# LCD_Controler_SCH.net
KiCad netlist of a schematic drawn in Altium Designer
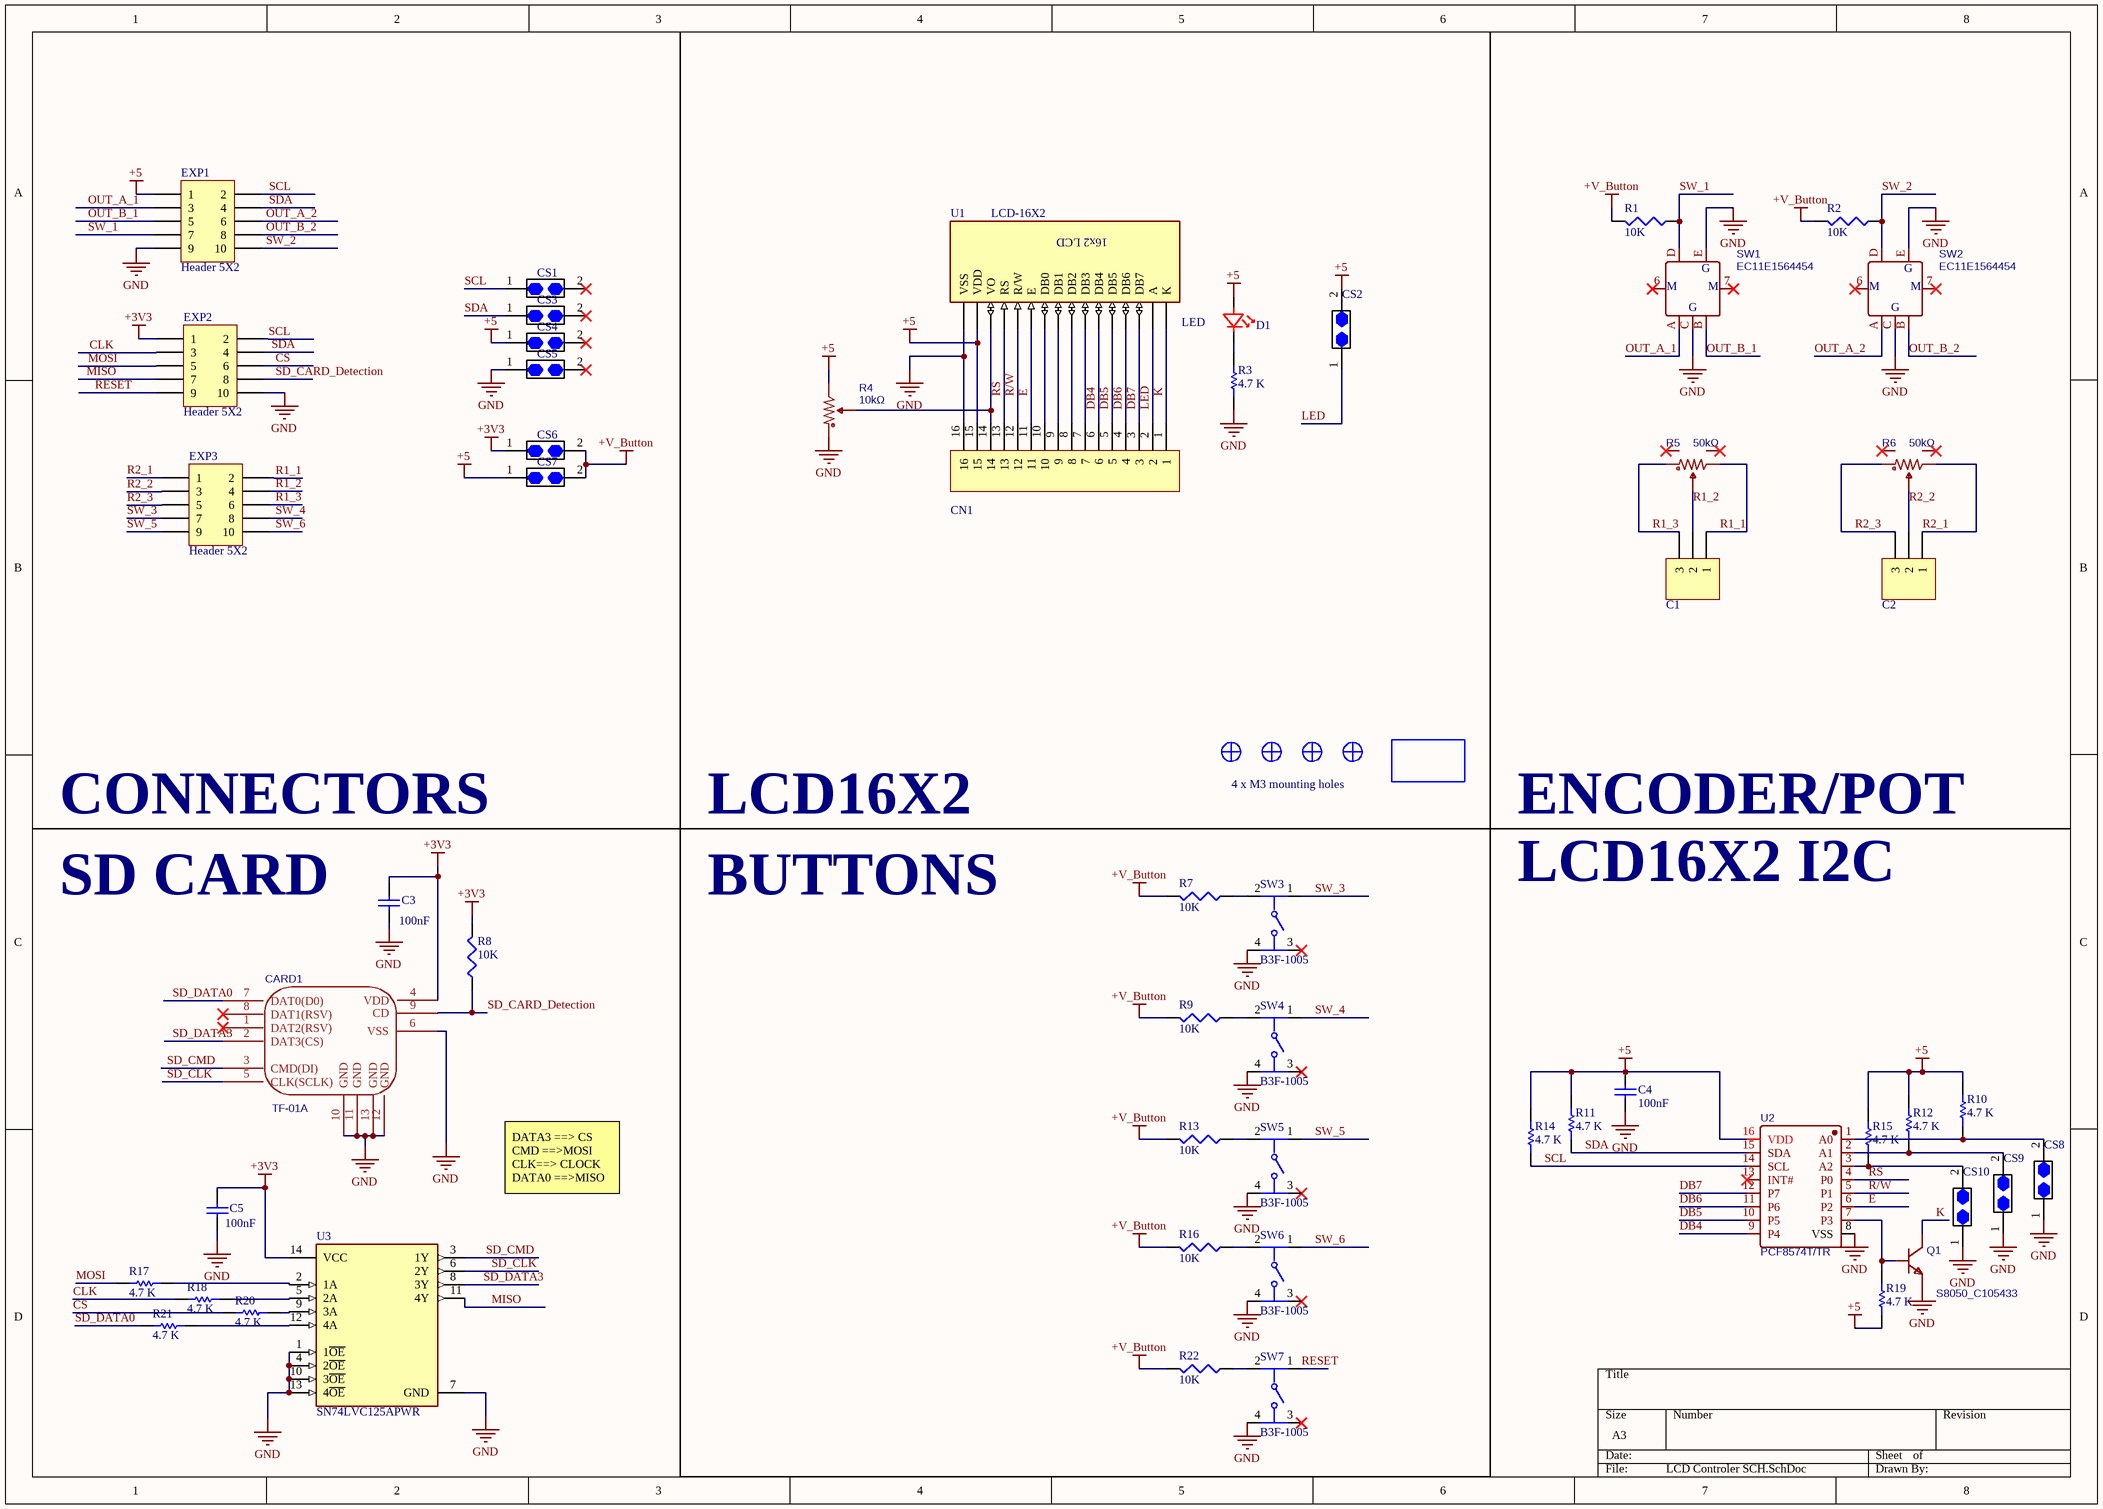
[diagram p0: LCD Controler SCH.SchDoc]

(export (version "E")
  (design (tool "Eeschema 10.0.6"))
  (components
    (comp (ref "C1")
      (value "Header 3")
      (footprint "HDR1X3-HEADER")
      (description "Header, 3-Pin")
      (fields (field (name "PUBLISHER") "Altium Limited"))
      (libsource (lib "Mylib") (part "Header 3"))
    )
    (comp (ref "C2")
      (value "Header 3")
      (footprint "HDR1X3-HEADER")
      (description "Header, 3-Pin")
      (fields (field (name "PUBLISHER") "Altium Limited"))
      (libsource (lib "Mylib") (part "Header 3"))
    )
    (comp (ref "C3")
      (value "100nF")
      (footprint "Cap 1608-0603")
      (description "CAP CER 0.1UF 50V X7R 0603/0805")
      (fields (field (name "MFR") "TORCH") (field (name "LCSC PART NUMBER") "C138340"))
      (libsource (lib "RUMBA_v2") (part "CapC-0603-100nF"))
    )
    (comp (ref "C4")
      (value "100nF")
      (footprint "Cap 1608-0603")
      (description "CAP CER 0.1UF 50V X7R 0603/0805")
      (fields (field (name "MFR") "TORCH") (field (name "LCSC PART NUMBER") "C138340"))
      (libsource (lib "RUMBA_v2") (part "CapC-0603-100nF"))
    )
    (comp (ref "C5")
      (value "100nF")
      (footprint "Cap 1608-0603")
      (description "CAP CER 0.1UF 50V X7R 0603/0805")
      (fields (field (name "MFR") "TORCH") (field (name "LCSC PART NUMBER") "C138340"))
      (libsource (lib "RUMBA_v2") (part "CapC-0603-100nF"))
    )
    (comp (ref "CARD1")
      (value "TF-01A")
      (footprint "TF-SMD_TF-01A2")
      (description "LCSC Part # C91145\r\nManufacturer Korean Hroparts Elec")
      (fields (field (name "BOM_SUPPLIER PART") "C91145"))
      (libsource (lib "Rumba_plus_esp") (part "TF-01A"))
    )
    (comp (ref "CN1")
      (value "Header 16")
      (footprint "HDR1X16-HEADER")
      (description "male")
      (fields (field (name "PUBLISHER") "Altium Limited"))
      (libsource (lib "Mylib") (part "Header 16x1"))
    )
    (comp (ref "CS1") (value "CHEVRON") (footprint "CHEV") (libsource (lib "Mylib") (part "CHEVRON")))
    (comp (ref "CS2") (value "CHEVRON") (footprint "CHEV") (libsource (lib "Mylib") (part "CHEVRON")))
    (comp (ref "CS3") (value "CHEVRON") (footprint "CHEV") (libsource (lib "Mylib") (part "CHEVRON")))
    (comp (ref "CS4") (value "CHEVRON") (footprint "CHEV") (libsource (lib "Mylib") (part "CHEVRON")))
    (comp (ref "CS5") (value "CHEVRON") (footprint "CHEV") (libsource (lib "Mylib") (part "CHEVRON")))
    (comp (ref "CS6") (value "CHEVRON") (footprint "CHEV") (libsource (lib "Mylib") (part "CHEVRON")))
    (comp (ref "CS7") (value "CHEVRON") (footprint "CHEV") (libsource (lib "Mylib") (part "CHEVRON")))
    (comp (ref "CS8") (value "CHEVRON") (footprint "CHEV") (libsource (lib "Mylib") (part "CHEVRON")))
    (comp (ref "CS9") (value "CHEVRON") (footprint "CHEV") (libsource (lib "Mylib") (part "CHEVRON")))
    (comp (ref "CS10") (value "CHEVRON") (footprint "CHEV") (libsource (lib "Mylib") (part "CHEVRON")))
    (comp (ref "D1")
      (value "LED")
      (footprint "LED_0603R")
      (fields (field (name "MFR") "LITEON"))
      (libsource (lib "Schlib_PbA") (part "Diode_LED"))
    )
    (comp (ref "EXP1")
      (value "Header 5X2")
      (footprint "HDR2X5_exp Iner only\\")
      (description "Header, 5-Pin, Dual row")
      (fields (field (name "PUBLISHER") "Altium Limited"))
      (libsource (lib "Mylib") (part "Header 5X2"))
    )
    (comp (ref "EXP2")
      (value "Header 5X2")
      (footprint "HDR2X5_exp Iner only\\")
      (description "Header, 5-Pin, Dual row")
      (fields (field (name "PUBLISHER") "Altium Limited"))
      (libsource (lib "Mylib") (part "Header 5X2"))
    )
    (comp (ref "EXP3")
      (value "Header 5X2")
      (footprint "HDR2X5_exp Iner only\\")
      (description "Header, 5-Pin, Dual row")
      (fields (field (name "PUBLISHER") "Altium Limited"))
      (libsource (lib "Mylib") (part "Header 5X2"))
    )
    (comp (ref "OS logo1") (value "Logo") (footprint "OS LOGO TOP") (libsource (lib "gc") (part "Logo")))
    (comp (ref "Q1")
      (value "S8050_C105433")
      (footprint "SOT-23-3_L2.9-W1.6-P1.90-LS2.8-BR")
      (description "25V 300mW 120@50mA,1V 500mA NPN SOT-23 Bipolar Transistors - BJT ROHS")
      (fields (field (name "MANUFACTURER") "CJ(江苏长电/长晶)") (field (name "MANUFACTURER PART") "S8050"))
      (libsource (lib "Mylib") (part "S8050"))
    )
    (comp (ref "R1")
      (value "10K")
      (footprint "RES 1608-0603")
      (description "RES SMD 10K OHM 1% 1/10W 0603")
      (fields (field (name "Comment") "resistor"))
      (libsource (lib "RUMBA_v2") (part "Res-0603-10K"))
    )
    (comp (ref "R2")
      (value "10K")
      (footprint "RES 1608-0603")
      (description "RES SMD 10K OHM 1% 1/10W 0603")
      (fields (field (name "Comment") "resistor"))
      (libsource (lib "RUMBA_v2") (part "Res-0603-10K"))
    )
    (comp (ref "R3")
      (value "4.7 K")
      (footprint "0805")
      (fields (field (name "LCSC PART NUMBER") "C60816"))
      (libsource (lib "Mylib") (part "Res-0805"))
    )
    (comp (ref "R4")
      (value "10kΩ")
      (footprint "RES-ADJ-TH_3362P")
      (description "±10% 10kΩ Plugin Variable Resistors/Potentiometers ROHS")
      (fields
        (field (name "MANUFACTURER") "BOCHEN(博晨)")
        (field (name "MANUFACTURER PART") "3362P-1-103")
        (field (name "CONTRIBUTOR") "LCSC")
      )
      (libsource (lib "Mylib") (part "3362P-1-103"))
    )
    (comp (ref "R5")
      (value "50kΩ")
      (footprint "RES-ADJ-TH_RK09L1140A5P")
      (fields
        (field (name "MANUFACTURER") "ALPSALPINE(阿尔卑斯阿尔派)")
        (field (name "MANUFACTURER PART") "RK09L1140A5P")
        (field (name "CONTRIBUTOR") "LCSC")
      )
      (libsource (lib "Mylib") (part "Potentiometers  50kΩ vertical"))
    )
    (comp (ref "R6")
      (value "50kΩ")
      (footprint "RES-ADJ-TH_RK09L1140A5P")
      (fields
        (field (name "MANUFACTURER") "ALPSALPINE(阿尔卑斯阿尔派)")
        (field (name "MANUFACTURER PART") "RK09L1140A5P")
        (field (name "CONTRIBUTOR") "LCSC")
      )
      (libsource (lib "Mylib") (part "Potentiometers  50kΩ vertical"))
    )
    (comp (ref "R7")
      (value "10K")
      (footprint "RES 1608-0603")
      (description "RES SMD 10K OHM 1% 1/10W 0603")
      (fields (field (name "Comment") "resistor"))
      (libsource (lib "RUMBA_v2") (part "Res-0603-10K"))
    )
    (comp (ref "R8")
      (value "10K")
      (footprint "RES 1608-0603")
      (description "RES SMD 10K OHM 1% 1/10W 0603")
      (fields (field (name "Comment") "resistor"))
      (libsource (lib "RUMBA_v2") (part "Res-0603-10K"))
    )
    (comp (ref "R9")
      (value "10K")
      (footprint "RES 1608-0603")
      (description "RES SMD 10K OHM 1% 1/10W 0603")
      (fields (field (name "Comment") "resistor"))
      (libsource (lib "RUMBA_v2") (part "Res-0603-10K"))
    )
    (comp (ref "R10")
      (value "4.7 K")
      (footprint "0805")
      (fields (field (name "LCSC PART NUMBER") "C60816"))
      (libsource (lib "Mylib") (part "Res-0805"))
    )
    (comp (ref "R11")
      (value "4.7 K")
      (footprint "0805")
      (fields (field (name "LCSC PART NUMBER") "C60816"))
      (libsource (lib "Mylib") (part "Res-0805"))
    )
    (comp (ref "R12")
      (value "4.7 K")
      (footprint "0805")
      (fields (field (name "LCSC PART NUMBER") "C60816"))
      (libsource (lib "Mylib") (part "Res-0805"))
    )
    (comp (ref "R13")
      (value "10K")
      (footprint "RES 1608-0603")
      (description "RES SMD 10K OHM 1% 1/10W 0603")
      (fields (field (name "Comment") "resistor"))
      (libsource (lib "RUMBA_v2") (part "Res-0603-10K"))
    )
    (comp (ref "R14")
      (value "4.7 K")
      (footprint "0805")
      (fields (field (name "LCSC PART NUMBER") "C60816"))
      (libsource (lib "Mylib") (part "Res-0805"))
    )
    (comp (ref "R15")
      (value "4.7 K")
      (footprint "0805")
      (fields (field (name "LCSC PART NUMBER") "C60816"))
      (libsource (lib "Mylib") (part "Res-0805"))
    )
    (comp (ref "R16")
      (value "10K")
      (footprint "RES 1608-0603")
      (description "RES SMD 10K OHM 1% 1/10W 0603")
      (fields (field (name "Comment") "resistor"))
      (libsource (lib "RUMBA_v2") (part "Res-0603-10K"))
    )
    (comp (ref "R17")
      (value "4.7 K")
      (footprint "0805")
      (fields (field (name "LCSC PART NUMBER") "C60816"))
      (libsource (lib "Mylib") (part "Res-0805"))
    )
    (comp (ref "R18")
      (value "4.7 K")
      (footprint "0805")
      (fields (field (name "LCSC PART NUMBER") "C60816"))
      (libsource (lib "Mylib") (part "Res-0805"))
    )
    (comp (ref "R19")
      (value "4.7 K")
      (footprint "0805")
      (fields (field (name "LCSC PART NUMBER") "C60816"))
      (libsource (lib "Mylib") (part "Res-0805"))
    )
    (comp (ref "R20")
      (value "4.7 K")
      (footprint "0805")
      (fields (field (name "LCSC PART NUMBER") "C60816"))
      (libsource (lib "Mylib") (part "Res-0805"))
    )
    (comp (ref "R21")
      (value "4.7 K")
      (footprint "0805")
      (fields (field (name "LCSC PART NUMBER") "C60816"))
      (libsource (lib "Mylib") (part "Res-0805"))
    )
    (comp (ref "R22")
      (value "10K")
      (footprint "RES 1608-0603")
      (description "RES SMD 10K OHM 1% 1/10W 0603")
      (fields (field (name "Comment") "resistor"))
      (libsource (lib "RUMBA_v2") (part "Res-0603-10K"))
    )
    (comp (ref "sc1") (value "Sraf") (footprint "Sraf 3mm - rupa 3.2") (libsource (lib "gc") (part "Sraf")))
    (comp (ref "sc2") (value "Sraf") (footprint "Sraf 3mm - rupa 3.2") (libsource (lib "gc") (part "Sraf")))
    (comp (ref "sc3") (value "Sraf") (footprint "Sraf 3mm - rupa 3.5") (libsource (lib "gc") (part "Sraf")))
    (comp (ref "sc4") (value "Sraf") (footprint "Sraf 3mm - rupa 3.5") (libsource (lib "gc") (part "Sraf")))
    (comp (ref "SW1")
      (value "EC11E1564454")
      (footprint "SW-TH_EC11E1564454")
      (description "Plugin Rotary Encoders ROHS")
      (fields (field (name "MANUFACTURER") "ALPSALPINE") (field (name "CONTRIBUTOR") "LCSC"))
      (libsource (lib "Mylib") (part "EC11E1564454"))
    )
    (comp (ref "SW2")
      (value "EC11E1564454")
      (footprint "SW-TH_EC11E1564454")
      (description "Plugin Rotary Encoders ROHS")
      (fields (field (name "MANUFACTURER") "ALPSALPINE") (field (name "CONTRIBUTOR") "LCSC"))
      (libsource (lib "Mylib") (part "EC11E1564454"))
    )
    (comp (ref "SW3")
      (value "B3F-1005")
      (footprint "FP-B3F-1005-MFG")
      (description "SWITCH TACTILE SPST-NO 0.05A 24V")
      (libsource (lib "Altium Content Vault") (part "b8895f3f4cefb76e1819d2863dba89b"))
    )
    (comp (ref "SW4")
      (value "B3F-1005")
      (footprint "FP-B3F-1005-MFG")
      (description "SWITCH TACTILE SPST-NO 0.05A 24V")
      (libsource (lib "Altium Content Vault") (part "b8895f3f4cefb76e1819d2863dba89b"))
    )
    (comp (ref "SW5")
      (value "B3F-1005")
      (footprint "FP-B3F-1005-MFG")
      (description "SWITCH TACTILE SPST-NO 0.05A 24V")
      (libsource (lib "Altium Content Vault") (part "b8895f3f4cefb76e1819d2863dba89b"))
    )
    (comp (ref "SW6")
      (value "B3F-1005")
      (footprint "FP-B3F-1005-MFG")
      (description "SWITCH TACTILE SPST-NO 0.05A 24V")
      (libsource (lib "Altium Content Vault") (part "b8895f3f4cefb76e1819d2863dba89b"))
    )
    (comp (ref "SW7")
      (value "B3F-1005")
      (footprint "FP-B3F-1005-MFG")
      (description "SWITCH TACTILE SPST-NO 0.05A 24V")
      (libsource (lib "Altium Content Vault") (part "b8895f3f4cefb76e1819d2863dba89b"))
    )
    (comp (ref "U1")
      (value "LCD-16X2")
      (footprint "MODULE_LCD-16X2")
      (description "Display Development Tools 16x2 Black on Green Char LCD w Backlight")
      (fields (field (name "MF") "Gravitech"))
      (libsource (lib "Mylib") (part "LCD-16X2"))
    )
    (comp (ref "U2")
      (value "PCF8574T/TR")
      (footprint "SO-16_L10.3-W7.5-P1.27-LS10.3-BL")
      (description "Communication Interface Chip/UART/485/232/I/O Expanders")
      (fields (field (name "MANUFACTURER") "HGSEMI(华冠)") (field (name "CONTRIBUTOR") "lcsc"))
      (libsource (lib "Mylib") (part "PCF8574T/TR"))
    )
    (comp (ref "U3")
      (value "SN74LVC125APWR")
      (footprint "FP-PW0014A-IPC_B")
      (description "IC BUF NON-INVERT 3.6V 14TSSOP")
      (libsource (lib "Altium Content Vault") (part "0c185306b27c65c3e4a0d950f37c68a"))
    )
  )
  (nets
    (net (code "1") (name "+3V3") (class "Default")
      (node (ref "C3") (pin "1") (pinfunction "1_1") (pintype "passive"))
      (node (ref "C5") (pin "2") (pinfunction "2_2") (pintype "passive"))
      (node (ref "CARD1") (pin "4") (pinfunction "VDD_4") (pintype "passive"))
      (node (ref "CS6") (pin "1") (pinfunction "1_1") (pintype "passive"))
      (node (ref "EXP2") (pin "1") (pinfunction "1_1") (pintype "passive"))
      (node (ref "R8") (pin "2") (pinfunction "2_2") (pintype "passive"))
      (node (ref "U3") (pin "14") (pinfunction "VCC_14") (pintype "power_in"))
    )
    (net (code "2") (name "+5") (class "Default")
      (node (ref "C4") (pin "1") (pinfunction "1_1") (pintype "passive"))
      (node (ref "CN1") (pin "15") (pinfunction "15_15") (pintype "passive"))
      (node (ref "CS2") (pin "2") (pinfunction "2_2") (pintype "passive"))
      (node (ref "CS4") (pin "1") (pinfunction "1_1") (pintype "passive"))
      (node (ref "CS7") (pin "1") (pinfunction "1_1") (pintype "passive"))
      (node (ref "D1") (pin "1") (pinfunction "1_1") (pintype "passive"))
      (node (ref "EXP1") (pin "1") (pinfunction "1_1") (pintype "passive"))
      (node (ref "R10") (pin "2") (pinfunction "2_2") (pintype "passive"))
      (node (ref "R11") (pin "2") (pinfunction "2_2") (pintype "passive"))
      (node (ref "R12") (pin "2") (pinfunction "2_2") (pintype "passive"))
      (node (ref "R14") (pin "2") (pinfunction "2_2") (pintype "passive"))
      (node (ref "R15") (pin "2") (pinfunction "2_2") (pintype "passive"))
      (node (ref "R19") (pin "1") (pinfunction "1_1") (pintype "passive"))
      (node (ref "R4") (pin "3") (pinfunction "3_3") (pintype "passive"))
      (node (ref "U1") (pin "2") (pinfunction "VDD_2") (pintype "power_in"))
      (node (ref "U2") (pin "16") (pinfunction "VDD_16") (pintype "passive"))
    )
    (net (code "3") (name "+V_Button") (class "Default")
      (node (ref "CS6") (pin "2") (pinfunction "2_2") (pintype "passive"))
      (node (ref "CS7") (pin "2") (pinfunction "2_2") (pintype "passive"))
      (node (ref "R1") (pin "2") (pinfunction "2_2") (pintype "passive"))
      (node (ref "R13") (pin "2") (pinfunction "2_2") (pintype "passive"))
      (node (ref "R16") (pin "2") (pinfunction "2_2") (pintype "passive"))
      (node (ref "R2") (pin "2") (pinfunction "2_2") (pintype "passive"))
      (node (ref "R22") (pin "2") (pinfunction "2_2") (pintype "passive"))
      (node (ref "R7") (pin "2") (pinfunction "2_2") (pintype "passive"))
      (node (ref "R9") (pin "2") (pinfunction "2_2") (pintype "passive"))
    )
    (net (code "4") (name "/CLK") (class "Default")
      (node (ref "EXP2") (pin "3") (pinfunction "3_3") (pintype "passive"))
      (node (ref "R18") (pin "2") (pinfunction "2_2") (pintype "passive"))
    )
    (net (code "5") (name "/CS") (class "Default")
      (node (ref "EXP2") (pin "6") (pinfunction "6_6") (pintype "passive"))
      (node (ref "R20") (pin "2") (pinfunction "2_2") (pintype "passive"))
    )
    (net (code "6") (name "/DB4") (class "Default")
      (node (ref "CN1") (pin "6") (pinfunction "6_6") (pintype "passive"))
      (node (ref "U1") (pin "11") (pinfunction "DB4_11") (pintype "bidirectional"))
      (node (ref "U2") (pin "9") (pinfunction "P4_9") (pintype "passive"))
    )
    (net (code "7") (name "/DB5") (class "Default")
      (node (ref "CN1") (pin "5") (pinfunction "5_5") (pintype "passive"))
      (node (ref "U1") (pin "12") (pinfunction "DB5_12") (pintype "bidirectional"))
      (node (ref "U2") (pin "10") (pinfunction "P5_10") (pintype "passive"))
    )
    (net (code "8") (name "/DB6") (class "Default")
      (node (ref "CN1") (pin "4") (pinfunction "4_4") (pintype "passive"))
      (node (ref "U1") (pin "13") (pinfunction "DB6_13") (pintype "bidirectional"))
      (node (ref "U2") (pin "11") (pinfunction "P6_11") (pintype "passive"))
    )
    (net (code "9") (name "/DB7") (class "Default")
      (node (ref "CN1") (pin "3") (pinfunction "3_3") (pintype "passive"))
      (node (ref "U1") (pin "14") (pinfunction "DB7_14") (pintype "bidirectional"))
      (node (ref "U2") (pin "12") (pinfunction "P7_12") (pintype "passive"))
    )
    (net (code "10") (name "/E") (class "Default")
      (node (ref "CN1") (pin "11") (pinfunction "11_11") (pintype "passive"))
      (node (ref "U1") (pin "6") (pinfunction "E_6") (pintype "input"))
      (node (ref "U2") (pin "6") (pinfunction "P2_6") (pintype "passive"))
    )
    (net (code "11") (name "/K") (class "Default")
      (node (ref "CN1") (pin "1") (pinfunction "1_1") (pintype "passive"))
      (node (ref "Q1") (pin "3") (pinfunction "3_3") (pintype "passive"))
      (node (ref "U1") (pin "16") (pinfunction "K_16") (pintype "power_in"))
    )
    (net (code "12") (name "/LED") (class "Default")
      (node (ref "CN1") (pin "2") (pinfunction "2_2") (pintype "passive"))
      (node (ref "CS2") (pin "1") (pinfunction "1_1") (pintype "passive"))
      (node (ref "U1") (pin "15") (pinfunction "A_15") (pintype "power_in"))
    )
    (net (code "13") (name "/MISO") (class "Default")
      (node (ref "EXP2") (pin "7") (pinfunction "7_7") (pintype "passive"))
      (node (ref "U3") (pin "11") (pinfunction "4Y_11") (pintype "output"))
    )
    (net (code "14") (name "/MOSI") (class "Default")
      (node (ref "EXP2") (pin "5") (pinfunction "5_5") (pintype "passive"))
      (node (ref "R17") (pin "2") (pinfunction "2_2") (pintype "passive"))
    )
    (net (code "15") (name "/OUT_A_1") (class "Default")
      (node (ref "EXP1") (pin "3") (pinfunction "3_3") (pintype "passive"))
      (node (ref "SW1") (pin "A") (pinfunction "A_A") (pintype "passive"))
    )
    (net (code "16") (name "/OUT_A_2") (class "Default")
      (node (ref "EXP1") (pin "6") (pinfunction "6_6") (pintype "passive"))
      (node (ref "SW2") (pin "A") (pinfunction "A_A") (pintype "passive"))
    )
    (net (code "17") (name "/OUT_B_1") (class "Default")
      (node (ref "EXP1") (pin "5") (pinfunction "5_5") (pintype "passive"))
      (node (ref "SW1") (pin "B") (pinfunction "B_B") (pintype "passive"))
    )
    (net (code "18") (name "/OUT_B_2") (class "Default")
      (node (ref "EXP1") (pin "8") (pinfunction "8_8") (pintype "passive"))
      (node (ref "SW2") (pin "B") (pinfunction "B_B") (pintype "passive"))
    )
    (net (code "19") (name "/R1_1") (class "Default")
      (node (ref "C1") (pin "1") (pinfunction "1_1") (pintype "passive"))
      (node (ref "EXP3") (pin "2") (pinfunction "2_2") (pintype "passive"))
      (node (ref "R5") (pin "3") (pinfunction "3_3") (pintype "passive"))
    )
    (net (code "20") (name "/R1_2") (class "Default")
      (node (ref "C1") (pin "2") (pinfunction "2_2") (pintype "passive"))
      (node (ref "EXP3") (pin "4") (pinfunction "4_4") (pintype "passive"))
      (node (ref "R5") (pin "2") (pinfunction "2_2") (pintype "passive"))
    )
    (net (code "21") (name "/R1_3") (class "Default")
      (node (ref "C1") (pin "3") (pinfunction "3_3") (pintype "passive"))
      (node (ref "EXP3") (pin "6") (pinfunction "6_6") (pintype "passive"))
      (node (ref "R5") (pin "1") (pinfunction "1_1") (pintype "passive"))
    )
    (net (code "22") (name "/R2_1") (class "Default")
      (node (ref "C2") (pin "1") (pinfunction "1_1") (pintype "passive"))
      (node (ref "EXP3") (pin "1") (pinfunction "1_1") (pintype "passive"))
      (node (ref "R6") (pin "3") (pinfunction "3_3") (pintype "passive"))
    )
    (net (code "23") (name "/R2_2") (class "Default")
      (node (ref "C2") (pin "2") (pinfunction "2_2") (pintype "passive"))
      (node (ref "EXP3") (pin "3") (pinfunction "3_3") (pintype "passive"))
      (node (ref "R6") (pin "2") (pinfunction "2_2") (pintype "passive"))
    )
    (net (code "24") (name "/R2_3") (class "Default")
      (node (ref "C2") (pin "3") (pinfunction "3_3") (pintype "passive"))
      (node (ref "EXP3") (pin "5") (pinfunction "5_5") (pintype "passive"))
      (node (ref "R6") (pin "1") (pinfunction "1_1") (pintype "passive"))
    )
    (net (code "25") (name "/RESET") (class "Default")
      (node (ref "EXP2") (pin "9") (pinfunction "9_9") (pintype "passive"))
      (node (ref "SW7") (pin "1") (pinfunction "1_1") (pintype "passive"))
    )
    (net (code "26") (name "/RS") (class "Default")
      (node (ref "CN1") (pin "13") (pinfunction "13_13") (pintype "passive"))
      (node (ref "U1") (pin "4") (pinfunction "RS_4") (pintype "input"))
      (node (ref "U2") (pin "4") (pinfunction "P0_4") (pintype "passive"))
    )
    (net (code "27") (name "/R{slash}W") (class "Default")
      (node (ref "CN1") (pin "12") (pinfunction "12_12") (pintype "passive"))
      (node (ref "U1") (pin "5") (pinfunction "R/W_5") (pintype "input"))
      (node (ref "U2") (pin "5") (pinfunction "P1_5") (pintype "passive"))
    )
    (net (code "28") (name "/SCL") (class "Default")
      (node (ref "CS1") (pin "1") (pinfunction "1_1") (pintype "passive"))
      (node (ref "EXP1") (pin "2") (pinfunction "2_2") (pintype "passive"))
      (node (ref "EXP2") (pin "2") (pinfunction "2_2") (pintype "passive"))
      (node (ref "R14") (pin "1") (pinfunction "1_1") (pintype "passive"))
      (node (ref "U2") (pin "14") (pinfunction "SCL_14") (pintype "passive"))
    )
    (net (code "29") (name "/SDA") (class "Default")
      (node (ref "CS3") (pin "1") (pinfunction "1_1") (pintype "passive"))
      (node (ref "EXP1") (pin "4") (pinfunction "4_4") (pintype "passive"))
      (node (ref "EXP2") (pin "4") (pinfunction "4_4") (pintype "passive"))
      (node (ref "R11") (pin "1") (pinfunction "1_1") (pintype "passive"))
      (node (ref "U2") (pin "15") (pinfunction "SDA_15") (pintype "passive"))
    )
    (net (code "30") (name "/SD_CARD_Detection") (class "Default")
      (node (ref "CARD1") (pin "9") (pinfunction "CD_9") (pintype "passive"))
      (node (ref "EXP2") (pin "8") (pinfunction "8_8") (pintype "passive"))
      (node (ref "R8") (pin "1") (pinfunction "1_1") (pintype "passive"))
    )
    (net (code "31") (name "/SD_CLK") (class "Default")
      (node (ref "CARD1") (pin "5") (pinfunction "CLK(SCLK)_5") (pintype "passive"))
      (node (ref "U3") (pin "6") (pinfunction "2Y_6") (pintype "output"))
    )
    (net (code "32") (name "/SD_CMD") (class "Default")
      (node (ref "CARD1") (pin "3") (pinfunction "CMD(DI)_3") (pintype "passive"))
      (node (ref "U3") (pin "3") (pinfunction "1Y_3") (pintype "output"))
    )
    (net (code "33") (name "/SD_DATA0") (class "Default")
      (node (ref "CARD1") (pin "7") (pinfunction "DAT0(D0)_7") (pintype "passive"))
      (node (ref "R21") (pin "2") (pinfunction "2_2") (pintype "passive"))
    )
    (net (code "34") (name "/SD_DATA3") (class "Default")
      (node (ref "CARD1") (pin "2") (pinfunction "DAT3(CS)_2") (pintype "passive"))
      (node (ref "U3") (pin "8") (pinfunction "3Y_8") (pintype "output"))
    )
    (net (code "35") (name "/SW_1") (class "Default")
      (node (ref "EXP1") (pin "7") (pinfunction "7_7") (pintype "passive"))
      (node (ref "R1") (pin "1") (pinfunction "1_1") (pintype "passive"))
      (node (ref "SW1") (pin "D") (pinfunction "D_D") (pintype "passive"))
    )
    (net (code "36") (name "/SW_2") (class "Default")
      (node (ref "EXP1") (pin "10") (pinfunction "10_10") (pintype "passive"))
      (node (ref "R2") (pin "1") (pinfunction "1_1") (pintype "passive"))
      (node (ref "SW2") (pin "D") (pinfunction "D_D") (pintype "passive"))
    )
    (net (code "37") (name "/SW_3") (class "Default")
      (node (ref "EXP3") (pin "7") (pinfunction "7_7") (pintype "passive"))
      (node (ref "SW3") (pin "1") (pinfunction "1_1") (pintype "passive"))
    )
    (net (code "38") (name "/SW_4") (class "Default")
      (node (ref "EXP3") (pin "8") (pinfunction "8_8") (pintype "passive"))
      (node (ref "SW4") (pin "1") (pinfunction "1_1") (pintype "passive"))
    )
    (net (code "39") (name "/SW_5") (class "Default")
      (node (ref "EXP3") (pin "9") (pinfunction "9_9") (pintype "passive"))
      (node (ref "SW5") (pin "1") (pinfunction "1_1") (pintype "passive"))
    )
    (net (code "40") (name "/SW_6") (class "Default")
      (node (ref "EXP3") (pin "10") (pinfunction "10_10") (pintype "passive"))
      (node (ref "SW6") (pin "1") (pinfunction "1_1") (pintype "passive"))
    )
    (net (code "41") (name "GND") (class "Default")
      (node (ref "C3") (pin "2") (pinfunction "2_2") (pintype "passive"))
      (node (ref "C4") (pin "2") (pinfunction "2_2") (pintype "passive"))
      (node (ref "C5") (pin "1") (pinfunction "1_1") (pintype "passive"))
      (node (ref "CARD1") (pin "10") (pinfunction "GND_10") (pintype "passive"))
      (node (ref "CARD1") (pin "11") (pinfunction "GND_11") (pintype "passive"))
      (node (ref "CARD1") (pin "12") (pinfunction "GND_12") (pintype "passive"))
      (node (ref "CARD1") (pin "13") (pinfunction "GND_13") (pintype "passive"))
      (node (ref "CARD1") (pin "6") (pinfunction "VSS_6") (pintype "passive"))
      (node (ref "CN1") (pin "16") (pinfunction "16_16") (pintype "passive"))
      (node (ref "CS10") (pin "1") (pinfunction "1_1") (pintype "passive"))
      (node (ref "CS5") (pin "1") (pinfunction "1_1") (pintype "passive"))
      (node (ref "CS8") (pin "1") (pinfunction "1_1") (pintype "passive"))
      (node (ref "CS9") (pin "1") (pinfunction "1_1") (pintype "passive"))
      (node (ref "EXP1") (pin "9") (pinfunction "9_9") (pintype "passive"))
      (node (ref "EXP2") (pin "10") (pinfunction "10_10") (pintype "passive"))
      (node (ref "Q1") (pin "2") (pinfunction "2_2") (pintype "passive"))
      (node (ref "R3") (pin "1") (pinfunction "1_1") (pintype "passive"))
      (node (ref "R4") (pin "1") (pinfunction "1_1") (pintype "passive"))
      (node (ref "SW1") (pin "C") (pinfunction "C_C") (pintype "passive"))
      (node (ref "SW1") (pin "E") (pinfunction "E_E") (pintype "passive"))
      (node (ref "SW2") (pin "C") (pinfunction "C_C") (pintype "passive"))
      (node (ref "SW2") (pin "E") (pinfunction "E_E") (pintype "passive"))
      (node (ref "SW3") (pin "4") (pinfunction "4_4") (pintype "passive"))
      (node (ref "SW4") (pin "4") (pinfunction "4_4") (pintype "passive"))
      (node (ref "SW5") (pin "4") (pinfunction "4_4") (pintype "passive"))
      (node (ref "SW6") (pin "4") (pinfunction "4_4") (pintype "passive"))
      (node (ref "SW7") (pin "4") (pinfunction "4_4") (pintype "passive"))
      (node (ref "U1") (pin "1") (pinfunction "VSS_1") (pintype "power_in"))
      (node (ref "U2") (pin "8") (pinfunction "VSS_8") (pintype "passive"))
      (node (ref "U3") (pin "1") (pinfunction "1~{OE}_1") (pintype "input"))
      (node (ref "U3") (pin "10") (pinfunction "3~{OE}_10") (pintype "input"))
      (node (ref "U3") (pin "13") (pinfunction "4~{OE}_13") (pintype "input"))
      (node (ref "U3") (pin "4") (pinfunction "2~{OE}_4") (pintype "input"))
      (node (ref "U3") (pin "7") (pinfunction "GND_7") (pintype "power_in"))
    )
    (net (code "42") (name "Net-(D1-Pad2)") (class "Default")
      (node (ref "D1") (pin "2") (pinfunction "2_2") (pintype "passive"))
      (node (ref "R3") (pin "2") (pinfunction "2_2") (pintype "passive"))
    )
    (net (code "43") (name "Net-(R7-Pad1)") (class "Default")
      (node (ref "R7") (pin "1") (pinfunction "1_1") (pintype "passive"))
      (node (ref "SW3") (pin "2") (pinfunction "2_2") (pintype "passive"))
    )
    (net (code "44") (name "Net-(R9-Pad1)") (class "Default")
      (node (ref "R9") (pin "1") (pinfunction "1_1") (pintype "passive"))
      (node (ref "SW4") (pin "2") (pinfunction "2_2") (pintype "passive"))
    )
    (net (code "45") (name "Net-(R13-Pad1)") (class "Default")
      (node (ref "R13") (pin "1") (pinfunction "1_1") (pintype "passive"))
      (node (ref "SW5") (pin "2") (pinfunction "2_2") (pintype "passive"))
    )
    (net (code "46") (name "Net-(R16-Pad1)") (class "Default")
      (node (ref "R16") (pin "1") (pinfunction "1_1") (pintype "passive"))
      (node (ref "SW6") (pin "2") (pinfunction "2_2") (pintype "passive"))
    )
    (net (code "47") (name "Net-(R22-Pad1)") (class "Default")
      (node (ref "R22") (pin "1") (pinfunction "1_1") (pintype "passive"))
      (node (ref "SW7") (pin "2") (pinfunction "2_2") (pintype "passive"))
    )
    (net (code "48") (name "Net-(U1-DB0)") (class "Default")
      (node (ref "CN1") (pin "10") (pinfunction "10_10") (pintype "passive"))
      (node (ref "U1") (pin "7") (pinfunction "DB0_7") (pintype "bidirectional"))
    )
    (net (code "49") (name "Net-(U1-DB1)") (class "Default")
      (node (ref "CN1") (pin "9") (pinfunction "9_9") (pintype "passive"))
      (node (ref "U1") (pin "8") (pinfunction "DB1_8") (pintype "bidirectional"))
    )
    (net (code "50") (name "Net-(U1-DB2)") (class "Default")
      (node (ref "CN1") (pin "8") (pinfunction "8_8") (pintype "passive"))
      (node (ref "U1") (pin "9") (pinfunction "DB2_9") (pintype "bidirectional"))
    )
    (net (code "51") (name "Net-(U1-DB3)") (class "Default")
      (node (ref "CN1") (pin "7") (pinfunction "7_7") (pintype "passive"))
      (node (ref "U1") (pin "10") (pinfunction "DB3_10") (pintype "bidirectional"))
    )
    (net (code "52") (name "Net-(U1-VO)") (class "Default")
      (node (ref "CN1") (pin "14") (pinfunction "14_14") (pintype "passive"))
      (node (ref "R4") (pin "2") (pinfunction "2_2") (pintype "passive"))
      (node (ref "U1") (pin "3") (pinfunction "VO_3") (pintype "bidirectional"))
    )
    (net (code "53") (name "Net-(U2-A0)") (class "Default")
      (node (ref "CS8") (pin "2") (pinfunction "2_2") (pintype "passive"))
      (node (ref "R10") (pin "1") (pinfunction "1_1") (pintype "passive"))
      (node (ref "U2") (pin "1") (pinfunction "A0_1") (pintype "passive"))
    )
    (net (code "54") (name "Net-(U2-A1)") (class "Default")
      (node (ref "CS9") (pin "2") (pinfunction "2_2") (pintype "passive"))
      (node (ref "R12") (pin "1") (pinfunction "1_1") (pintype "passive"))
      (node (ref "U2") (pin "2") (pinfunction "A1_2") (pintype "passive"))
    )
    (net (code "55") (name "Net-(U2-A2)") (class "Default")
      (node (ref "CS10") (pin "2") (pinfunction "2_2") (pintype "passive"))
      (node (ref "R15") (pin "1") (pinfunction "1_1") (pintype "passive"))
      (node (ref "U2") (pin "3") (pinfunction "A2_3") (pintype "passive"))
    )
    (net (code "56") (name "Net-(U2-P3)") (class "Default")
      (node (ref "Q1") (pin "1") (pinfunction "1_1") (pintype "passive"))
      (node (ref "R19") (pin "2") (pinfunction "2_2") (pintype "passive"))
      (node (ref "U2") (pin "7") (pinfunction "P3_7") (pintype "passive"))
    )
    (net (code "57") (name "Net-(U3-1A)") (class "Default")
      (node (ref "R17") (pin "1") (pinfunction "1_1") (pintype "passive"))
      (node (ref "U3") (pin "2") (pinfunction "1A_2") (pintype "input"))
    )
    (net (code "58") (name "Net-(U3-2A)") (class "Default")
      (node (ref "R18") (pin "1") (pinfunction "1_1") (pintype "passive"))
      (node (ref "U3") (pin "5") (pinfunction "2A_5") (pintype "input"))
    )
    (net (code "59") (name "Net-(U3-3A)") (class "Default")
      (node (ref "R20") (pin "1") (pinfunction "1_1") (pintype "passive"))
      (node (ref "U3") (pin "9") (pinfunction "3A_9") (pintype "input"))
    )
    (net (code "60") (name "Net-(U3-4A)") (class "Default")
      (node (ref "R21") (pin "1") (pinfunction "1_1") (pintype "passive"))
      (node (ref "U3") (pin "12") (pinfunction "4A_12") (pintype "input"))
    )
    (net (code "61") (name "unconnected-(CARD1-DAT1(RSV)-Pad8)") (class "Default")
      (node (ref "CARD1") (pin "8") (pinfunction "DAT1(RSV)_8") (pintype "passive+no_connect"))
    )
    (net (code "62") (name "unconnected-(CARD1-DAT2(RSV)-Pad1)") (class "Default")
      (node (ref "CARD1") (pin "1") (pinfunction "DAT2(RSV)_1") (pintype "passive+no_connect"))
    )
    (net (code "63") (name "unconnected-(CS1-Pad2)") (class "Default")
      (node (ref "CS1") (pin "2") (pinfunction "2_2") (pintype "passive+no_connect"))
    )
    (net (code "64") (name "unconnected-(CS3-Pad2)") (class "Default")
      (node (ref "CS3") (pin "2") (pinfunction "2_2") (pintype "passive+no_connect"))
    )
    (net (code "65") (name "unconnected-(CS4-Pad2)") (class "Default")
      (node (ref "CS4") (pin "2") (pinfunction "2_2") (pintype "passive+no_connect"))
    )
    (net (code "66") (name "unconnected-(CS5-Pad2)") (class "Default")
      (node (ref "CS5") (pin "2") (pinfunction "2_2") (pintype "passive+no_connect"))
    )
    (net (code "67") (name "unconnected-(R5-Pad4)") (class "Default")
      (node (ref "R5") (pin "4") (pinfunction "4_4") (pintype "passive+no_connect"))
    )
    (net (code "68") (name "unconnected-(R5-Pad5)") (class "Default")
      (node (ref "R5") (pin "5") (pinfunction "5_5") (pintype "passive+no_connect"))
    )
    (net (code "69") (name "unconnected-(R6-Pad4)") (class "Default")
      (node (ref "R6") (pin "4") (pinfunction "4_4") (pintype "passive+no_connect"))
    )
    (net (code "70") (name "unconnected-(R6-Pad5)") (class "Default")
      (node (ref "R6") (pin "5") (pinfunction "5_5") (pintype "passive+no_connect"))
    )
    (net (code "71") (name "unconnected-(SW1-EH-Pad6)") (class "Default")
      (node (ref "SW1") (pin "6") (pinfunction "EH_6") (pintype "passive+no_connect"))
    )
    (net (code "72") (name "unconnected-(SW1-EH-Pad7)") (class "Default")
      (node (ref "SW1") (pin "7") (pinfunction "EH_7") (pintype "passive+no_connect"))
    )
    (net (code "73") (name "unconnected-(SW2-EH-Pad6)") (class "Default")
      (node (ref "SW2") (pin "6") (pinfunction "EH_6") (pintype "passive+no_connect"))
    )
    (net (code "74") (name "unconnected-(SW2-EH-Pad7)") (class "Default")
      (node (ref "SW2") (pin "7") (pinfunction "EH_7") (pintype "passive+no_connect"))
    )
    (net (code "75") (name "unconnected-(SW3-Pad3)") (class "Default")
      (node (ref "SW3") (pin "3") (pinfunction "3_3") (pintype "passive+no_connect"))
    )
    (net (code "76") (name "unconnected-(SW4-Pad3)") (class "Default")
      (node (ref "SW4") (pin "3") (pinfunction "3_3") (pintype "passive+no_connect"))
    )
    (net (code "77") (name "unconnected-(SW5-Pad3)") (class "Default")
      (node (ref "SW5") (pin "3") (pinfunction "3_3") (pintype "passive+no_connect"))
    )
    (net (code "78") (name "unconnected-(SW6-Pad3)") (class "Default")
      (node (ref "SW6") (pin "3") (pinfunction "3_3") (pintype "passive+no_connect"))
    )
    (net (code "79") (name "unconnected-(SW7-Pad3)") (class "Default")
      (node (ref "SW7") (pin "3") (pinfunction "3_3") (pintype "passive+no_connect"))
    )
    (net (code "80") (name "unconnected-(U2-INT#-Pad13)") (class "Default")
      (node (ref "U2") (pin "13") (pinfunction "INT#_13") (pintype "passive+no_connect"))
    )
  )
)
